# attinier84-motherboard-mk-1_0.net
KiCad netlist of a schematic drawn in EAGLE
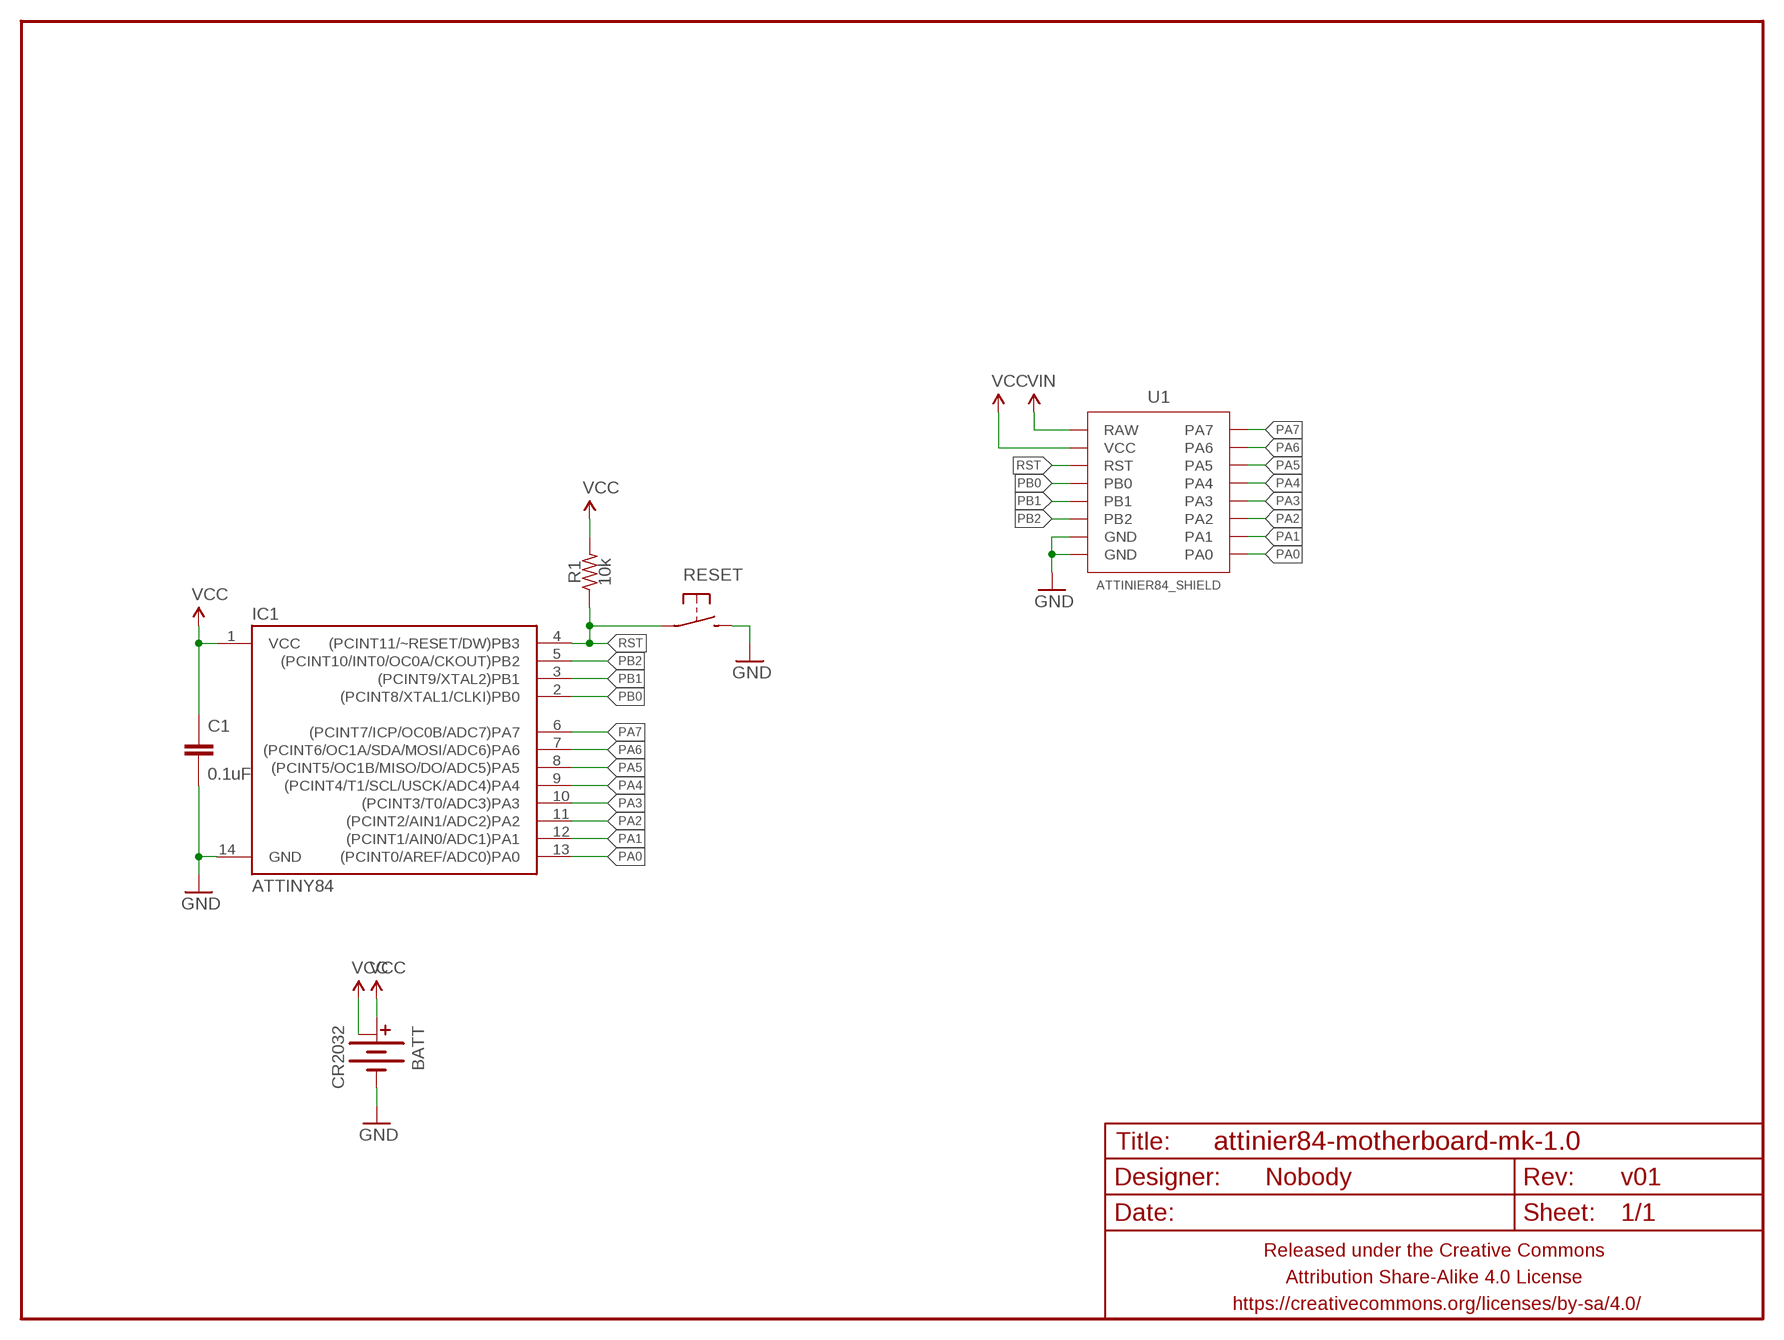
[diagram p0: schematic, sheet 1]

(export (version "E")
  (design (tool "Eeschema 10.0.6"))
  (components
    (comp (ref "BATT")
      (value "CR2032")
      (footprint "eagle-import:BATTCON_20MM_MINE")
      (libsource (lib "eagle-import") (part "BATTERY-COINCR2032_SMD"))
    )
    (comp (ref "C1")
      (value "0.1uF")
      (footprint "eagle-import:C0805")
      (libsource (lib "eagle-import") (part "CAPACITOR-CERAMICC0805"))
    )
    (comp (ref "FRAME1")
      (value "FRAME-LETTERNO_PACKAGE")
      (footprint "eagle-import:DUMMY")
      (fields (field (name "DESIGNER") "Nobody"))
      (libsource (lib "eagle-import") (part "FRAME-LETTERNO_PACKAGE"))
    )
    (comp (ref "IC1")
      (value "ATTINY84")
      (footprint "eagle-import:SO14")
      (libsource (lib "eagle-import") (part "ATTINY84"))
    )
    (comp (ref "R1")
      (value "10k")
      (footprint "eagle-import:R0805")
      (libsource (lib "eagle-import") (part "RESISTORR0805"))
    )
    (comp (ref "RESET")
      (value "SPST-NO-TACT6MM-SMD")
      (footprint "eagle-import:DTSM-6")
      (libsource (lib "eagle-import") (part "SPST-NO-TACT6MM-SMD"))
    )
    (comp (ref "U1")
      (value "ATTINIER84_SHIELD")
      (footprint "eagle-import:ATTINIER84_SHIELD")
      (libsource (lib "eagle-import") (part "ATTINIER84_SHIELD"))
    )
  )
  (nets
    (net (code "1") (name "GND") (class "Default")
      (node (ref "BATT") (pin "BOTTOM") (pinfunction "-_BOTTOM") (pintype "bidirectional"))
      (node (ref "C1") (pin "2") (pinfunction "2_2") (pintype "passive"))
      (node (ref "IC1") (pin "14") (pinfunction "GND_14") (pintype "bidirectional"))
      (node (ref "RESET") (pin "3") (pinfunction "2_3") (pintype "passive"))
      (node (ref "RESET") (pin "4") (pinfunction "2_4") (pintype "passive"))
      (node (ref "U1") (pin "GND@1") (pinfunction "GND_GND@1") (pintype "bidirectional"))
      (node (ref "U1") (pin "GND@2") (pinfunction "GND_GND@2") (pintype "bidirectional"))
    )
    (net (code "2") (name "PA0") (class "Default")
      (node (ref "IC1") (pin "13") (pinfunction "(PCINT0/AREF/ADC0)PA0_13") (pintype "bidirectional"))
      (node (ref "U1") (pin "PA0") (pinfunction "PA0_PA0") (pintype "bidirectional"))
    )
    (net (code "3") (name "PA1") (class "Default")
      (node (ref "IC1") (pin "12") (pinfunction "(PCINT1/AIN0/ADC1)PA1_12") (pintype "bidirectional"))
      (node (ref "U1") (pin "PA1") (pinfunction "PA1_PA1") (pintype "bidirectional"))
    )
    (net (code "4") (name "PA2") (class "Default")
      (node (ref "IC1") (pin "11") (pinfunction "(PCINT2/AIN1/ADC2)PA2_11") (pintype "bidirectional"))
      (node (ref "U1") (pin "PA2") (pinfunction "PA2_PA2") (pintype "bidirectional"))
    )
    (net (code "5") (name "PA3") (class "Default")
      (node (ref "IC1") (pin "10") (pinfunction "(PCINT3/T0/ADC3)PA3_10") (pintype "bidirectional"))
      (node (ref "U1") (pin "PA3") (pinfunction "PA3_PA3") (pintype "bidirectional"))
    )
    (net (code "6") (name "PA4") (class "Default")
      (node (ref "IC1") (pin "9") (pinfunction "(PCINT4/T1/SCL/USCK/ADC4)PA4_9") (pintype "bidirectional"))
      (node (ref "U1") (pin "PA4") (pinfunction "PA4_PA4") (pintype "bidirectional"))
    )
    (net (code "7") (name "PA5") (class "Default")
      (node (ref "IC1") (pin "8") (pinfunction "(PCINT5/OC1B/MISO/DO/ADC5)PA5_8") (pintype "bidirectional"))
      (node (ref "U1") (pin "PA5") (pinfunction "PA5_PA5") (pintype "bidirectional"))
    )
    (net (code "8") (name "PA6") (class "Default")
      (node (ref "IC1") (pin "7") (pinfunction "(PCINT6/OC1A/SDA/MOSI/ADC6)PA6_7") (pintype "bidirectional"))
      (node (ref "U1") (pin "PA6") (pinfunction "PA6_PA6") (pintype "bidirectional"))
    )
    (net (code "9") (name "PA7") (class "Default")
      (node (ref "IC1") (pin "6") (pinfunction "(PCINT7/ICP/OC0B/ADC7)PA7_6") (pintype "bidirectional"))
      (node (ref "U1") (pin "PA7") (pinfunction "PA7_PA7") (pintype "bidirectional"))
    )
    (net (code "10") (name "PB0") (class "Default")
      (node (ref "IC1") (pin "2") (pinfunction "(PCINT8/XTAL1/CLKI)PB0_2") (pintype "bidirectional"))
      (node (ref "U1") (pin "PB0") (pinfunction "PB0_PB0") (pintype "bidirectional"))
    )
    (net (code "11") (name "PB1") (class "Default")
      (node (ref "IC1") (pin "3") (pinfunction "(PCINT9/XTAL2)PB1_3") (pintype "bidirectional"))
      (node (ref "U1") (pin "PB1") (pinfunction "PB1_PB1") (pintype "bidirectional"))
    )
    (net (code "12") (name "PB2") (class "Default")
      (node (ref "IC1") (pin "5") (pinfunction "(PCINT10/INT0/OC0A/CKOUT)PB2_5") (pintype "bidirectional"))
      (node (ref "U1") (pin "PB2") (pinfunction "PB2_PB2") (pintype "bidirectional"))
    )
    (net (code "13") (name "RST") (class "Default")
      (node (ref "IC1") (pin "4") (pinfunction "(PCINT11/~{RESET/DW})PB3_4") (pintype "bidirectional"))
      (node (ref "R1") (pin "1") (pinfunction "1_1") (pintype "passive"))
      (node (ref "RESET") (pin "1") (pinfunction "1_1") (pintype "passive"))
      (node (ref "RESET") (pin "2") (pinfunction "1_2") (pintype "passive"))
      (node (ref "U1") (pin "RST") (pinfunction "RST_RST") (pintype "bidirectional"))
    )
    (net (code "14") (name "VCC") (class "Default")
      (node (ref "BATT") (pin "TOP@1") (pinfunction "+_TOP@1") (pintype "bidirectional"))
      (node (ref "BATT") (pin "TOP@2") (pinfunction "+1_TOP@2") (pintype "bidirectional"))
      (node (ref "C1") (pin "1") (pinfunction "1_1") (pintype "passive"))
      (node (ref "IC1") (pin "1") (pinfunction "VCC_1") (pintype "bidirectional"))
      (node (ref "R1") (pin "2") (pinfunction "2_2") (pintype "passive"))
      (node (ref "U1") (pin "VCC") (pinfunction "VCC_VCC") (pintype "bidirectional"))
    )
    (net (code "15") (name "VIN") (class "Default")
      (node (ref "U1") (pin "RAW") (pinfunction "RAW_RAW") (pintype "bidirectional"))
    )
  )
)
